# LabPower-FB.net
KiCad netlist of a schematic drawn in EAGLE
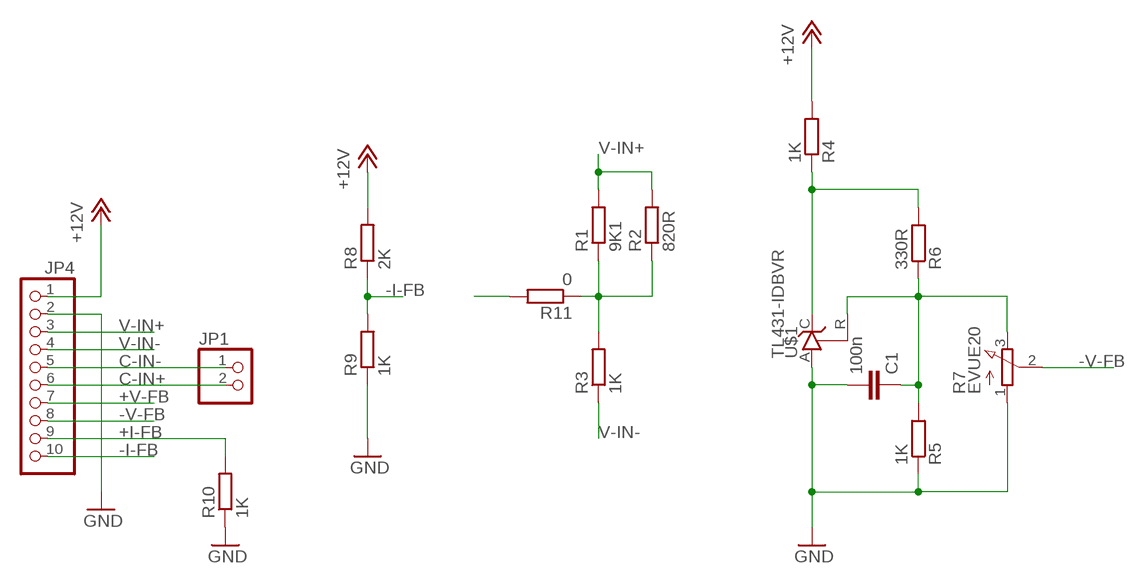
[diagram p0: schematic, sheet 1]

(export (version "E")
  (design (tool "Eeschema 10.0.6"))
  (components
    (comp (ref "C1")
      (value "100n")
      (footprint "eagle-import:C0805")
      (libsource (lib "eagle-import") (part "C-EUC0805"))
    )
    (comp (ref "JP1")
      (value "PINHD-1X2/90")
      (footprint "eagle-import:1X02_90")
      (libsource (lib "eagle-import") (part "PINHD-1X2/90"))
    )
    (comp (ref "JP4")
      (value "PINHD-1X10")
      (footprint "eagle-import:1X10")
      (libsource (lib "eagle-import") (part "PINHD-1X10"))
    )
    (comp (ref "R1")
      (value "9K1")
      (footprint "eagle-import:R0805")
      (libsource (lib "eagle-import") (part "R-EU_R0805"))
    )
    (comp (ref "R2")
      (value "820R")
      (footprint "eagle-import:R0805")
      (libsource (lib "eagle-import") (part "R-EU_R0805"))
    )
    (comp (ref "R3")
      (value "1K")
      (footprint "eagle-import:R0805")
      (libsource (lib "eagle-import") (part "R-EU_R0805"))
    )
    (comp (ref "R4")
      (value "1K")
      (footprint "eagle-import:R0805")
      (libsource (lib "eagle-import") (part "R-EU_R0805"))
    )
    (comp (ref "R5")
      (value "1K")
      (footprint "eagle-import:R0805")
      (libsource (lib "eagle-import") (part "R-EU_R0805"))
    )
    (comp (ref "R6")
      (value "330R")
      (footprint "eagle-import:R0805")
      (libsource (lib "eagle-import") (part "R-EU_R0805"))
    )
    (comp (ref "R7")
      (value "EVUE20")
      (footprint "eagle-import:EVUE")
      (libsource (lib "eagle-import") (part "EVUE20"))
    )
    (comp (ref "R8")
      (value "2K")
      (footprint "eagle-import:R0805")
      (libsource (lib "eagle-import") (part "R-EU_R0805"))
    )
    (comp (ref "R9")
      (value "1K")
      (footprint "eagle-import:R0805")
      (libsource (lib "eagle-import") (part "R-EU_R0805"))
    )
    (comp (ref "R10")
      (value "1K")
      (footprint "eagle-import:R0805")
      (libsource (lib "eagle-import") (part "R-EU_R0805"))
    )
    (comp (ref "R11")
      (value "0")
      (footprint "eagle-import:R0805")
      (libsource (lib "eagle-import") (part "R-EU_R0805"))
    )
    (comp (ref "U$1")
      (value "TL431-IDBVR")
      (footprint "eagle-import:SOT23-5")
      (libsource (lib "eagle-import") (part "TL431-IDBVR"))
    )
  )
  (nets
    (net (code "1") (name "+12V") (class "Default")
      (node (ref "JP4") (pin "1") (pinfunction "1_1") (pintype "passive"))
      (node (ref "R4") (pin "2") (pinfunction "2_2") (pintype "passive"))
      (node (ref "R8") (pin "2") (pinfunction "2_2") (pintype "passive"))
    )
    (net (code "2") (name "/+I-FB") (class "Default")
      (node (ref "JP4") (pin "9") (pinfunction "9_9") (pintype "passive"))
      (node (ref "R10") (pin "2") (pinfunction "2_2") (pintype "passive"))
    )
    (net (code "3") (name "/+V-FB") (class "Default")
      (node (ref "JP4") (pin "7") (pinfunction "7_7") (pintype "passive"))
      (node (ref "R11") (pin "2") (pinfunction "2_2") (pintype "passive"))
    )
    (net (code "4") (name "/-I-FB") (class "Default")
      (node (ref "JP4") (pin "10") (pinfunction "10_10") (pintype "passive"))
      (node (ref "R8") (pin "1") (pinfunction "1_1") (pintype "passive"))
      (node (ref "R9") (pin "2") (pinfunction "2_2") (pintype "passive"))
    )
    (net (code "5") (name "/-V-FB") (class "Default")
      (node (ref "JP4") (pin "8") (pinfunction "8_8") (pintype "passive"))
      (node (ref "R7") (pin "2") (pinfunction "S_2") (pintype "passive"))
    )
    (net (code "6") (name "/C-IN+") (class "Default")
      (node (ref "JP1") (pin "2") (pinfunction "2_2") (pintype "passive"))
      (node (ref "JP4") (pin "6") (pinfunction "6_6") (pintype "passive"))
    )
    (net (code "7") (name "/C-IN-") (class "Default")
      (node (ref "JP1") (pin "1") (pinfunction "1_1") (pintype "passive"))
      (node (ref "JP4") (pin "5") (pinfunction "5_5") (pintype "passive"))
    )
    (net (code "8") (name "/V-IN+") (class "Default")
      (node (ref "JP4") (pin "3") (pinfunction "3_3") (pintype "passive"))
      (node (ref "R1") (pin "2") (pinfunction "2_2") (pintype "passive"))
      (node (ref "R2") (pin "2") (pinfunction "2_2") (pintype "passive"))
    )
    (net (code "9") (name "/V-IN-") (class "Default")
      (node (ref "JP4") (pin "4") (pinfunction "4_4") (pintype "passive"))
      (node (ref "R3") (pin "1") (pinfunction "1_1") (pintype "passive"))
    )
    (net (code "10") (name "GND") (class "Default")
      (node (ref "C1") (pin "2") (pinfunction "2_2") (pintype "passive"))
      (node (ref "JP4") (pin "2") (pinfunction "2_2") (pintype "passive"))
      (node (ref "R10") (pin "1") (pinfunction "1_1") (pintype "passive"))
      (node (ref "R5") (pin "1") (pinfunction "1_1") (pintype "passive"))
      (node (ref "R7") (pin "1") (pinfunction "A_1") (pintype "passive"))
      (node (ref "R9") (pin "1") (pinfunction "1_1") (pintype "passive"))
      (node (ref "U$1") (pin "A") (pinfunction "A_A") (pintype "passive"))
    )
    (net (code "11") (name "Net-(R1-Pad1)") (class "Default")
      (node (ref "R1") (pin "1") (pinfunction "1_1") (pintype "passive"))
      (node (ref "R11") (pin "1") (pinfunction "1_1") (pintype "passive"))
      (node (ref "R2") (pin "1") (pinfunction "1_1") (pintype "passive"))
      (node (ref "R3") (pin "2") (pinfunction "2_2") (pintype "passive"))
    )
    (net (code "12") (name "Net-(R4-Pad1)") (class "Default")
      (node (ref "R4") (pin "1") (pinfunction "1_1") (pintype "passive"))
      (node (ref "R6") (pin "2") (pinfunction "2_2") (pintype "passive"))
      (node (ref "U$1") (pin "C") (pinfunction "C_C") (pintype "passive"))
    )
    (net (code "13") (name "Net-(R7-E)") (class "Default")
      (node (ref "C1") (pin "1") (pinfunction "1_1") (pintype "passive"))
      (node (ref "R5") (pin "2") (pinfunction "2_2") (pintype "passive"))
      (node (ref "R6") (pin "1") (pinfunction "1_1") (pintype "passive"))
      (node (ref "R7") (pin "3") (pinfunction "E_3") (pintype "passive"))
      (node (ref "U$1") (pin "R") (pinfunction "R_R") (pintype "passive"))
    )
  )
)
